# USB_UART_Converter.net
KiCad netlist of a schematic drawn in Altium Designer
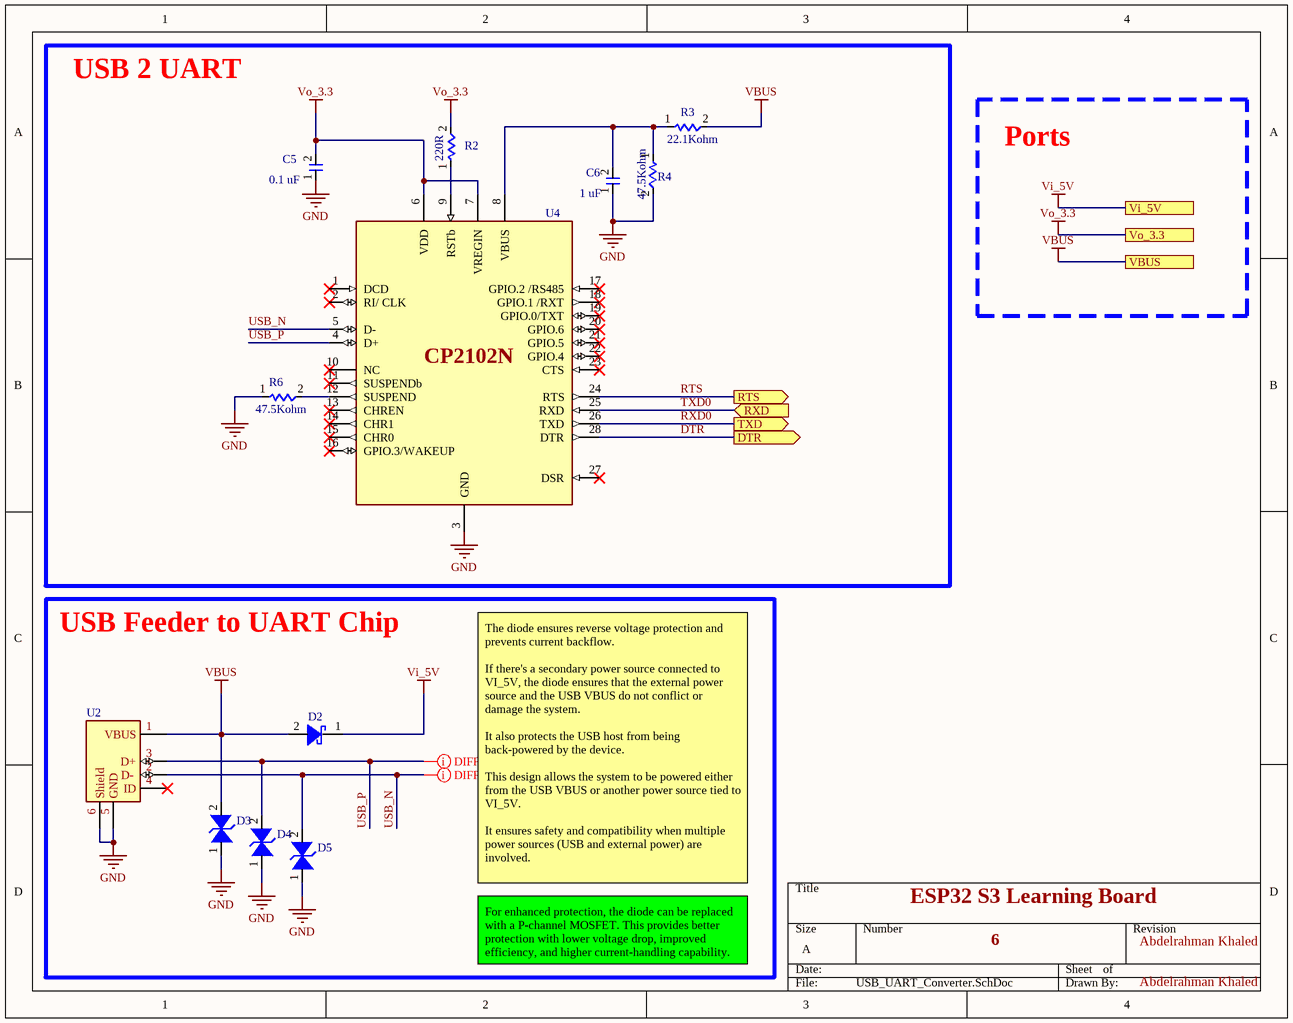
[diagram p0: USB_UART_Converter.SchDoc]

(export (version "E")
  (design (tool "Eeschema 10.0.6"))
  (components
    (comp (ref "C5")
      (value "0.1 uF")
      (footprint "Capacitor")
      (libsource (lib "ESP32_S3_Integrated_Library") (part "Capacitor"))
    )
    (comp (ref "C6")
      (value "1 uF")
      (footprint "Capacitor")
      (libsource (lib "ESP32_S3_Integrated_Library") (part "Capacitor"))
    )
    (comp (ref "D2")
      (value "0.2V Drop Volt")
      (footprint "Schoktty Diode")
      (description "NRVB120ESFT1G")
      (libsource (lib "ESP32_S3_Integrated_Library") (part "Schottky Diode"))
    )
    (comp (ref "D3")
      (value "TVS Diode")
      (footprint "TVS Diode")
      (libsource (lib "ESP32_S3_Integrated_Library") (part "TVS Diode"))
    )
    (comp (ref "D4")
      (value "TVS Diode")
      (footprint "TVS Diode")
      (libsource (lib "ESP32_S3_Integrated_Library") (part "TVS Diode"))
    )
    (comp (ref "D5")
      (value "TVS Diode")
      (footprint "TVS Diode")
      (libsource (lib "ESP32_S3_Integrated_Library") (part "TVS Diode"))
    )
    (comp (ref "R2")
      (value "220R")
      (footprint "Resistor")
      (libsource (lib "ESP32_S3_Integrated_Library") (part "Resistance"))
    )
    (comp (ref "R3")
      (value "22.1Kohm")
      (footprint "Resistor")
      (libsource (lib "ESP32_S3_Integrated_Library") (part "Resistance"))
    )
    (comp (ref "R4")
      (value "47.5Kohm")
      (footprint "Resistor")
      (libsource (lib "ESP32_S3_Integrated_Library") (part "Resistance"))
    )
    (comp (ref "R6")
      (value "47.5Kohm")
      (footprint "Resistor")
      (libsource (lib "ESP32_S3_Integrated_Library") (part "Resistance"))
    )
    (comp (ref "U2")
      (value "USB_B Micro")
      (footprint "USB8_Micro")
      (libsource (lib "ESP32_S3_Integrated_Library") (part "USB_B Micro"))
    )
    (comp (ref "U4")
      (value "CP2102N")
      (footprint "CP2102N")
      (libsource (lib "ESP32_S3_Integrated_Library") (part "CP2102N"))
    )
  )
  (nets
    (net (code "1") (name "/DTR") (class "Default")
      (node (ref "U4") (pin "28") (pinfunction "DTR_28") (pintype "output"))
    )
    (net (code "2") (name "/RTS") (class "Default")
      (node (ref "U4") (pin "24") (pinfunction "RTS_24") (pintype "output"))
    )
    (net (code "3") (name "/RXD0") (class "Default")
      (node (ref "U4") (pin "26") (pinfunction "TXD_26") (pintype "output"))
    )
    (net (code "4") (name "/TXD0") (class "Default")
      (node (ref "U4") (pin "25") (pinfunction "RXD_25") (pintype "input"))
    )
    (net (code "5") (name "/USB_N") (class "Default")
      (node (ref "D5") (pin "2") (pintype "passive"))
      (node (ref "U2") (pin "2") (pinfunction "D-_2") (pintype "bidirectional"))
      (node (ref "U4") (pin "5") (pinfunction "D-_5") (pintype "bidirectional"))
    )
    (net (code "6") (name "/USB_P") (class "Default")
      (node (ref "D4") (pin "2") (pintype "passive"))
      (node (ref "U2") (pin "3") (pinfunction "D+_3") (pintype "bidirectional"))
      (node (ref "U4") (pin "4") (pinfunction "D+_4") (pintype "bidirectional"))
    )
    (net (code "7") (name "GND") (class "Default")
      (node (ref "C5") (pin "1") (pinfunction "Pin_1_1") (pintype "passive"))
      (node (ref "C6") (pin "1") (pinfunction "Pin_1_1") (pintype "passive"))
      (node (ref "D3") (pin "1") (pintype "passive"))
      (node (ref "D4") (pin "1") (pintype "passive"))
      (node (ref "D5") (pin "1") (pintype "passive"))
      (node (ref "R4") (pin "2") (pinfunction "pin_2_2") (pintype "passive"))
      (node (ref "R6") (pin "1") (pinfunction "Pin_1_1") (pintype "passive"))
      (node (ref "U2") (pin "5") (pinfunction "GND_5") (pintype "power_in"))
      (node (ref "U2") (pin "6") (pinfunction "Shield_6") (pintype "power_in"))
      (node (ref "U4") (pin "3") (pinfunction "GND_3") (pintype "power_in"))
    )
    (net (code "8") (name "Net-(C6-Pin_2)") (class "Default")
      (node (ref "C6") (pin "2") (pinfunction "Pin_2_2") (pintype "passive"))
      (node (ref "R3") (pin "1") (pinfunction "Pin_1_1") (pintype "passive"))
      (node (ref "R4") (pin "1") (pinfunction "Pin_1_1") (pintype "passive"))
      (node (ref "U4") (pin "8") (pinfunction "VBUS_8") (pintype "power_in"))
    )
    (net (code "9") (name "Net-(R2-Pin_1)") (class "Default")
      (node (ref "R2") (pin "1") (pinfunction "Pin_1_1") (pintype "passive"))
      (node (ref "U4") (pin "9") (pinfunction "RSTb_9") (pintype "input"))
    )
    (net (code "10") (name "Net-(R6-pin_2)") (class "Default")
      (node (ref "R6") (pin "2") (pinfunction "pin_2_2") (pintype "passive"))
      (node (ref "U4") (pin "12") (pinfunction "SUSPEND_12") (pintype "output"))
    )
    (net (code "11") (name "VBUS") (class "Default")
      (node (ref "D2") (pin "2") (pintype "passive"))
      (node (ref "D3") (pin "2") (pintype "passive"))
      (node (ref "R3") (pin "2") (pinfunction "pin_2_2") (pintype "passive"))
      (node (ref "U2") (pin "1") (pinfunction "VBUS_1") (pintype "power_in"))
    )
    (net (code "12") (name "Vi_5V") (class "Default") (node (ref "D2") (pin "1") (pintype "passive")))
    (net (code "13") (name "Vo_3.3") (class "Default")
      (node (ref "C5") (pin "2") (pinfunction "Pin_2_2") (pintype "passive"))
      (node (ref "R2") (pin "2") (pinfunction "pin_2_2") (pintype "passive"))
      (node (ref "U4") (pin "6") (pinfunction "VDD_6") (pintype "power_in"))
      (node (ref "U4") (pin "7") (pinfunction "VREGIN_7") (pintype "power_in"))
    )
    (net (code "14") (name "unconnected-(U2-ID-Pad4)") (class "Default")
      (node (ref "U2") (pin "4") (pinfunction "ID_4") (pintype "passive+no_connect"))
    )
    (net (code "15") (name "unconnected-(U4-CHR0-Pad15)") (class "Default")
      (node (ref "U4") (pin "15") (pinfunction "CHR0_15") (pintype "output+no_connect"))
    )
    (net (code "16") (name "unconnected-(U4-CHR1-Pad14)") (class "Default")
      (node (ref "U4") (pin "14") (pinfunction "CHR1_14") (pintype "output+no_connect"))
    )
    (net (code "17") (name "unconnected-(U4-CHREN-Pad13)") (class "Default")
      (node (ref "U4") (pin "13") (pinfunction "CHREN_13") (pintype "output+no_connect"))
    )
    (net (code "18") (name "unconnected-(U4-CTS-Pad23)") (class "Default")
      (node (ref "U4") (pin "23") (pinfunction "CTS_23") (pintype "input+no_connect"))
    )
    (net (code "19") (name "unconnected-(U4-DCD-Pad1)") (class "Default")
      (node (ref "U4") (pin "1") (pinfunction "DCD_1") (pintype "input+no_connect"))
    )
    (net (code "20") (name "unconnected-(U4-DSR-Pad27)") (class "Default")
      (node (ref "U4") (pin "27") (pinfunction "DSR_27") (pintype "input+no_connect"))
    )
    (net (code "21") (name "unconnected-(U4-GPIO.0{slash}TXT-Pad19)") (class "Default")
      (node (ref "U4") (pin "19") (pinfunction "GPIO.0/TXT_19") (pintype "bidirectional+no_connect"))
    )
    (net (code "22") (name "unconnected-(U4-GPIO.1_{slash}RXT-Pad18)") (class "Default")
      (node (ref "U4") (pin "18") (pinfunction "GPIO.1_/RXT_18") (pintype "output+no_connect"))
    )
    (net (code "23") (name "unconnected-(U4-GPIO.2_{slash}RS485-Pad17)") (class "Default")
      (node (ref "U4") (pin "17") (pinfunction "GPIO.2_/RS485_17") (pintype "input+no_connect"))
    )
    (net (code "24") (name "unconnected-(U4-GPIO.3{slash}WAKEUP-Pad16)") (class "Default")
      (node (ref "U4") (pin "16") (pinfunction "GPIO.3/WAKEUP_16") (pintype "bidirectional+no_connect"))
    )
    (net (code "25") (name "unconnected-(U4-NC-Pad10)") (class "Default")
      (node (ref "U4") (pin "10") (pinfunction "NC_10") (pintype "open_emitter+no_connect"))
    )
    (net (code "26") (name "unconnected-(U4-RI{slash}_CLK-Pad2)") (class "Default")
      (node (ref "U4") (pin "2") (pinfunction "RI/_CLK_2") (pintype "bidirectional+no_connect"))
    )
    (net (code "27") (name "unconnected-(U4-SUSPENDb-Pad11)") (class "Default")
      (node (ref "U4") (pin "11") (pinfunction "SUSPENDb_11") (pintype "output+no_connect"))
    )
    (net (code "28") (name "unconnected-(U4-_GPIO.4-Pad22)") (class "Default")
      (node (ref "U4") (pin "22") (pinfunction "_GPIO.4_22") (pintype "bidirectional+no_connect"))
    )
    (net (code "29") (name "unconnected-(U4-_GPIO.5-Pad21)") (class "Default")
      (node (ref "U4") (pin "21") (pinfunction "_GPIO.5_21") (pintype "bidirectional+no_connect"))
    )
    (net (code "30") (name "unconnected-(U4-_GPIO.6-Pad20)") (class "Default")
      (node (ref "U4") (pin "20") (pinfunction "_GPIO.6_20") (pintype "bidirectional+no_connect"))
    )
  )
)
